# rj45-breakout-9_3.net
KiCad netlist of a schematic drawn in EAGLE
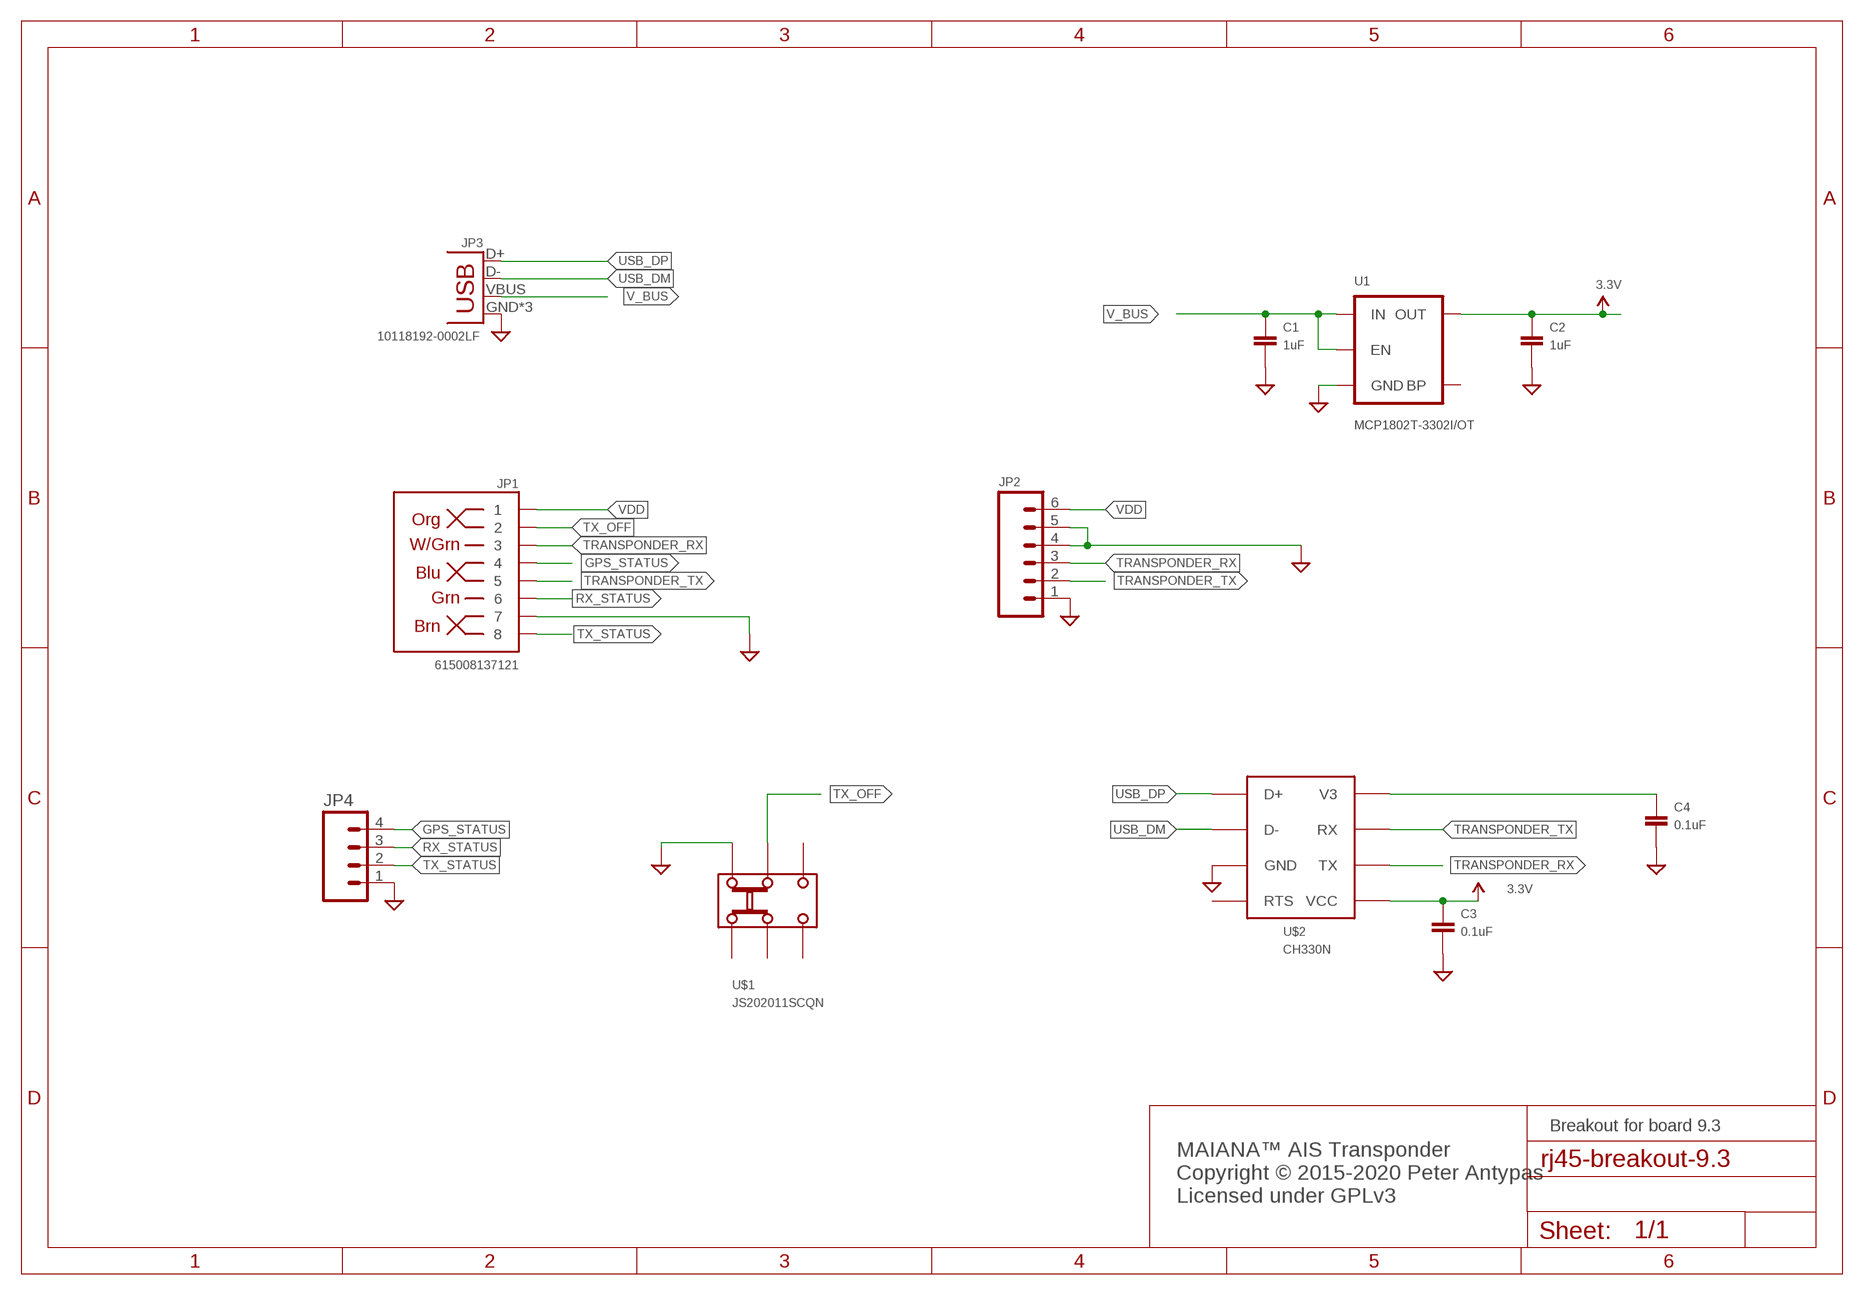
[diagram p0: schematic, sheet 1]

(export (version "E")
  (design (tool "Eeschema 10.0.6"))
  (components
    (comp (ref "C1")
      (value "1uF")
      (footprint "eagle-import:0603")
      (libsource (lib "eagle-import") (part "CAPACITOR0603"))
    )
    (comp (ref "C2")
      (value "1uF")
      (footprint "eagle-import:0603")
      (libsource (lib "eagle-import") (part "CAPACITOR0603"))
    )
    (comp (ref "C3")
      (value "0.1uF")
      (footprint "eagle-import:0603")
      (libsource (lib "eagle-import") (part "CAPACITOR0603"))
    )
    (comp (ref "C4")
      (value "0.1uF")
      (footprint "eagle-import:0603")
      (libsource (lib "eagle-import") (part "CAPACITOR0603"))
    )
    (comp (ref "JP1")
      (value "615008137121")
      (footprint "eagle-import:RJ45-8")
      (libsource (lib "eagle-import") (part "RJ45-8PTH"))
    )
    (comp (ref "JP2")
      (value "M06SILK_FEMALE_PTH")
      (footprint "eagle-import:1X06")
      (libsource (lib "eagle-import") (part "M06SILK_FEMALE_PTH"))
    )
    (comp (ref "JP3")
      (value "10118192-0002LF")
      (footprint "eagle-import:USB-MICROB")
      (libsource (lib "eagle-import") (part "USB-MICROB"))
    )
    (comp (ref "JP4")
      (value "M04PTH")
      (footprint "eagle-import:1X04")
      (libsource (lib "eagle-import") (part "M04PTH"))
    )
    (comp (ref "U$1")
      (value "JS202011SCQN")
      (footprint "eagle-import:DPDT-SMD")
      (libsource (lib "eagle-import") (part "JS202011SCQN"))
    )
    (comp (ref "U$2")
      (value "CH330N")
      (footprint "eagle-import:SOIC-8")
      (libsource (lib "eagle-import") (part "CH330N"))
    )
    (comp (ref "U1")
      (value "MCP1802T-3302I/OT")
      (footprint "eagle-import:SOT23-5")
      (libsource (lib "eagle-import") (part "V_REG_LDOSMD"))
    )
  )
  (nets
    (net (code "1") (name "3.3V") (class "Default")
      (node (ref "C2") (pin "P$1") (pinfunction "P$1_P$1") (pintype "bidirectional"))
      (node (ref "C3") (pin "P$1") (pinfunction "P$1_P$1") (pintype "bidirectional"))
      (node (ref "U$2") (pin "5") (pinfunction "VCC_5") (pintype "bidirectional"))
      (node (ref "U1") (pin "5") (pinfunction "OUT_5") (pintype "passive"))
    )
    (net (code "2") (name "GND") (class "Default")
      (node (ref "C1") (pin "P$2") (pinfunction "P$2_P$2") (pintype "bidirectional"))
      (node (ref "C2") (pin "P$2") (pinfunction "P$2_P$2") (pintype "bidirectional"))
      (node (ref "C3") (pin "P$2") (pinfunction "P$2_P$2") (pintype "bidirectional"))
      (node (ref "C4") (pin "P$2") (pinfunction "P$2_P$2") (pintype "bidirectional"))
      (node (ref "JP1") (pin "7") (pinfunction "7_7") (pintype "bidirectional"))
      (node (ref "JP2") (pin "1") (pinfunction "1_1") (pintype "passive"))
      (node (ref "JP2") (pin "4") (pinfunction "4_4") (pintype "passive"))
      (node (ref "JP2") (pin "5") (pinfunction "5_5") (pintype "passive"))
      (node (ref "JP3") (pin "GND") (pinfunction "GND_GND") (pintype "bidirectional"))
      (node (ref "JP3") (pin "MT1") (pinfunction "GND_MT1") (pintype "bidirectional"))
      (node (ref "JP3") (pin "MT2") (pinfunction "GND_MT2") (pintype "bidirectional"))
      (node (ref "JP4") (pin "1") (pinfunction "1_1") (pintype "passive"))
      (node (ref "U$1") (pin "P$6") (pinfunction "P$6_P$6") (pintype "bidirectional"))
      (node (ref "U$2") (pin "3") (pinfunction "GND_3") (pintype "bidirectional"))
      (node (ref "U1") (pin "2") (pinfunction "GND_2") (pintype "input"))
    )
    (net (code "3") (name "GPS_STATUS") (class "Default")
      (node (ref "JP1") (pin "4") (pinfunction "4_4") (pintype "bidirectional"))
      (node (ref "JP4") (pin "4") (pinfunction "4_4") (pintype "passive"))
    )
    (net (code "4") (name "Net-(U$2-V3)") (class "Default")
      (node (ref "C4") (pin "P$1") (pinfunction "P$1_P$1") (pintype "bidirectional"))
      (node (ref "U$2") (pin "8") (pinfunction "V3_8") (pintype "bidirectional"))
    )
    (net (code "5") (name "RX_STATUS") (class "Default")
      (node (ref "JP1") (pin "6") (pinfunction "6_6") (pintype "bidirectional"))
      (node (ref "JP4") (pin "3") (pinfunction "3_3") (pintype "passive"))
    )
    (net (code "6") (name "TRANSPONDER_RX") (class "Default")
      (node (ref "JP1") (pin "3") (pinfunction "3_3") (pintype "bidirectional"))
      (node (ref "JP2") (pin "3") (pinfunction "3_3") (pintype "passive"))
      (node (ref "U$2") (pin "6") (pinfunction "TX_6") (pintype "bidirectional"))
    )
    (net (code "7") (name "TRANSPONDER_TX") (class "Default")
      (node (ref "JP1") (pin "5") (pinfunction "5_5") (pintype "bidirectional"))
      (node (ref "JP2") (pin "2") (pinfunction "2_2") (pintype "passive"))
      (node (ref "U$2") (pin "7") (pinfunction "RX_7") (pintype "bidirectional"))
    )
    (net (code "8") (name "TX_OFF") (class "Default")
      (node (ref "JP1") (pin "2") (pinfunction "2_2") (pintype "bidirectional"))
      (node (ref "U$1") (pin "P$5") (pinfunction "P$5_P$5") (pintype "bidirectional"))
    )
    (net (code "9") (name "TX_STATUS") (class "Default")
      (node (ref "JP1") (pin "8") (pinfunction "8_8") (pintype "bidirectional"))
      (node (ref "JP4") (pin "2") (pinfunction "2_2") (pintype "passive"))
    )
    (net (code "10") (name "USB_DM") (class "Default")
      (node (ref "JP3") (pin "D-") (pinfunction "D-_D-") (pintype "bidirectional"))
      (node (ref "U$2") (pin "2") (pinfunction "D-_2") (pintype "bidirectional"))
    )
    (net (code "11") (name "USB_DP") (class "Default")
      (node (ref "JP3") (pin "D+") (pinfunction "D+_D+") (pintype "bidirectional"))
      (node (ref "U$2") (pin "1") (pinfunction "D+_1") (pintype "bidirectional"))
    )
    (net (code "12") (name "VDD") (class "Default")
      (node (ref "JP1") (pin "1") (pinfunction "1_1") (pintype "bidirectional"))
      (node (ref "JP2") (pin "6") (pinfunction "6_6") (pintype "passive"))
    )
    (net (code "13") (name "V_BUS") (class "Default")
      (node (ref "C1") (pin "P$1") (pinfunction "P$1_P$1") (pintype "bidirectional"))
      (node (ref "JP3") (pin "VBUS") (pinfunction "VBUS_VBUS") (pintype "bidirectional"))
      (node (ref "U1") (pin "1") (pinfunction "IN_1") (pintype "input"))
      (node (ref "U1") (pin "3") (pinfunction "EN_3") (pintype "input"))
    )
    (net (code "14") (name "unconnected-(U$1-PadP$1)") (class "Default")
      (node (ref "U$1") (pin "P$1") (pinfunction "P$1_P$1") (pintype "bidirectional"))
    )
    (net (code "15") (name "unconnected-(U$1-PadP$2)") (class "Default")
      (node (ref "U$1") (pin "P$2") (pinfunction "P$2_P$2") (pintype "bidirectional"))
    )
    (net (code "16") (name "unconnected-(U$1-PadP$3)") (class "Default")
      (node (ref "U$1") (pin "P$3") (pinfunction "P$3_P$3") (pintype "bidirectional"))
    )
    (net (code "17") (name "unconnected-(U$1-PadP$4)") (class "Default")
      (node (ref "U$1") (pin "P$4") (pinfunction "P$4_P$4") (pintype "bidirectional"))
    )
    (net (code "18") (name "unconnected-(U$2-RTS-Pad4)") (class "Default")
      (node (ref "U$2") (pin "4") (pinfunction "RTS_4") (pintype "bidirectional"))
    )
    (net (code "19") (name "unconnected-(U1-BP-Pad4)") (class "Default")
      (node (ref "U1") (pin "4") (pinfunction "BP_4") (pintype "input"))
    )
  )
)
